# Input_Board.net
KiCad netlist of a schematic drawn in EAGLE
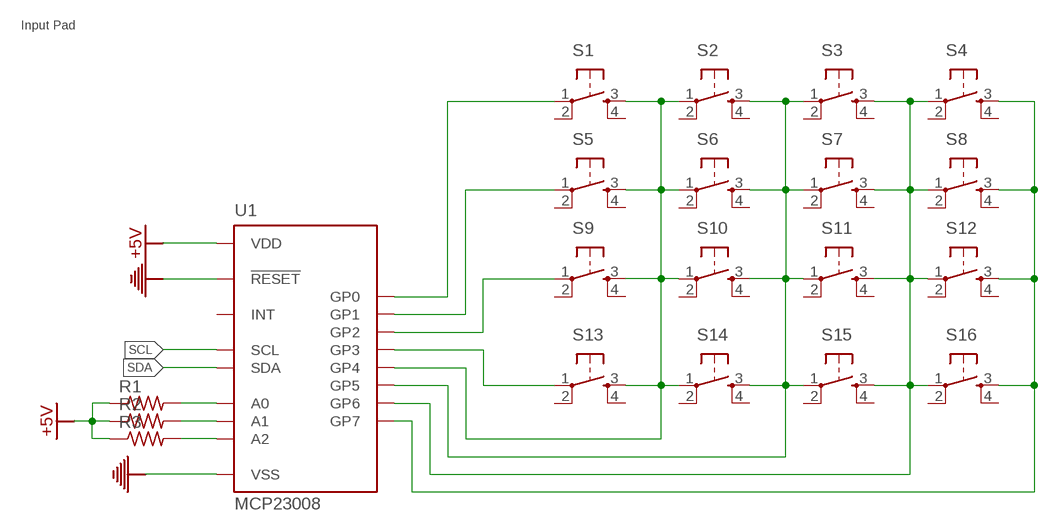
[diagram p0: schematic, sheet 1]

(export (version "E")
  (design (tool "Eeschema 10.0.6"))
  (components
    (comp (ref "R1")
      (value "R-US_M0805")
      (footprint "eagle-import:M0805")
      (libsource (lib "eagle-import") (part "R-US_M0805"))
    )
    (comp (ref "R2")
      (value "R-US_M0805")
      (footprint "eagle-import:M0805")
      (libsource (lib "eagle-import") (part "R-US_M0805"))
    )
    (comp (ref "R3")
      (value "R-US_M0805")
      (footprint "eagle-import:M0805")
      (libsource (lib "eagle-import") (part "R-US_M0805"))
    )
    (comp (ref "S1")
      (value "TAC_SWITCHPTH")
      (footprint "eagle-import:TACTILE-PTH")
      (libsource (lib "eagle-import") (part "TAC_SWITCHPTH"))
    )
    (comp (ref "S2")
      (value "TAC_SWITCHPTH")
      (footprint "eagle-import:TACTILE-PTH")
      (libsource (lib "eagle-import") (part "TAC_SWITCHPTH"))
    )
    (comp (ref "S3")
      (value "TAC_SWITCHPTH")
      (footprint "eagle-import:TACTILE-PTH")
      (libsource (lib "eagle-import") (part "TAC_SWITCHPTH"))
    )
    (comp (ref "S4")
      (value "TAC_SWITCHPTH")
      (footprint "eagle-import:TACTILE-PTH")
      (libsource (lib "eagle-import") (part "TAC_SWITCHPTH"))
    )
    (comp (ref "S5")
      (value "TAC_SWITCHPTH")
      (footprint "eagle-import:TACTILE-PTH")
      (libsource (lib "eagle-import") (part "TAC_SWITCHPTH"))
    )
    (comp (ref "S6")
      (value "TAC_SWITCHPTH")
      (footprint "eagle-import:TACTILE-PTH")
      (libsource (lib "eagle-import") (part "TAC_SWITCHPTH"))
    )
    (comp (ref "S7")
      (value "TAC_SWITCHPTH")
      (footprint "eagle-import:TACTILE-PTH")
      (libsource (lib "eagle-import") (part "TAC_SWITCHPTH"))
    )
    (comp (ref "S8")
      (value "TAC_SWITCHPTH")
      (footprint "eagle-import:TACTILE-PTH")
      (libsource (lib "eagle-import") (part "TAC_SWITCHPTH"))
    )
    (comp (ref "S9")
      (value "TAC_SWITCHPTH")
      (footprint "eagle-import:TACTILE-PTH")
      (libsource (lib "eagle-import") (part "TAC_SWITCHPTH"))
    )
    (comp (ref "S10")
      (value "TAC_SWITCHPTH")
      (footprint "eagle-import:TACTILE-PTH")
      (libsource (lib "eagle-import") (part "TAC_SWITCHPTH"))
    )
    (comp (ref "S11")
      (value "TAC_SWITCHPTH")
      (footprint "eagle-import:TACTILE-PTH")
      (libsource (lib "eagle-import") (part "TAC_SWITCHPTH"))
    )
    (comp (ref "S12")
      (value "TAC_SWITCHPTH")
      (footprint "eagle-import:TACTILE-PTH")
      (libsource (lib "eagle-import") (part "TAC_SWITCHPTH"))
    )
    (comp (ref "S13")
      (value "TAC_SWITCHPTH")
      (footprint "eagle-import:TACTILE-PTH")
      (libsource (lib "eagle-import") (part "TAC_SWITCHPTH"))
    )
    (comp (ref "S14")
      (value "TAC_SWITCHPTH")
      (footprint "eagle-import:TACTILE-PTH")
      (libsource (lib "eagle-import") (part "TAC_SWITCHPTH"))
    )
    (comp (ref "S15")
      (value "TAC_SWITCHPTH")
      (footprint "eagle-import:TACTILE-PTH")
      (libsource (lib "eagle-import") (part "TAC_SWITCHPTH"))
    )
    (comp (ref "S16")
      (value "TAC_SWITCHPTH")
      (footprint "eagle-import:TACTILE-PTH")
      (libsource (lib "eagle-import") (part "TAC_SWITCHPTH"))
    )
    (comp (ref "U1")
      (value "MCP23008")
      (footprint "eagle-import:SOIC")
      (libsource (lib "eagle-import") (part "MCP23008"))
    )
  )
  (nets
    (net (code "1") (name "+5V") (class "Default")
      (node (ref "R1") (pin "1") (pinfunction "1_1") (pintype "passive"))
      (node (ref "R2") (pin "1") (pinfunction "1_1") (pintype "passive"))
      (node (ref "R3") (pin "1") (pinfunction "1_1") (pintype "passive"))
      (node (ref "U1") (pin "P$18") (pinfunction "VDD_P$18") (pintype "power_in"))
    )
    (net (code "2") (name "GND") (class "Default")
      (node (ref "U1") (pin "P$6") (pinfunction "~{RESET}_P$6") (pintype "input"))
      (node (ref "U1") (pin "P$9") (pinfunction "VSS_P$9") (pintype "power_in"))
    )
    (net (code "3") (name "Net-(U1-A0)") (class "Default")
      (node (ref "R1") (pin "2") (pinfunction "2_2") (pintype "passive"))
      (node (ref "U1") (pin "P$5") (pinfunction "A0_P$5") (pintype "input"))
    )
    (net (code "4") (name "Net-(U1-A1)") (class "Default")
      (node (ref "R2") (pin "2") (pinfunction "2_2") (pintype "passive"))
      (node (ref "U1") (pin "P$4") (pinfunction "A1_P$4") (pintype "input"))
    )
    (net (code "5") (name "Net-(U1-A2)") (class "Default")
      (node (ref "R3") (pin "2") (pinfunction "2_2") (pintype "passive"))
      (node (ref "U1") (pin "P$3") (pinfunction "A2_P$3") (pintype "input"))
    )
    (net (code "6") (name "Net-(U1-GP0)") (class "Default")
      (node (ref "S1") (pin "1") (pinfunction "1_1") (pintype "passive"))
      (node (ref "U1") (pin "P$10") (pinfunction "GP0_P$10") (pintype "bidirectional"))
    )
    (net (code "7") (name "Net-(U1-GP1)") (class "Default")
      (node (ref "S5") (pin "1") (pinfunction "1_1") (pintype "passive"))
      (node (ref "U1") (pin "P$11") (pinfunction "GP1_P$11") (pintype "bidirectional"))
    )
    (net (code "8") (name "Net-(U1-GP2)") (class "Default")
      (node (ref "S9") (pin "1") (pinfunction "1_1") (pintype "passive"))
      (node (ref "U1") (pin "P$12") (pinfunction "GP2_P$12") (pintype "bidirectional"))
    )
    (net (code "9") (name "Net-(U1-GP3)") (class "Default")
      (node (ref "S13") (pin "1") (pinfunction "1_1") (pintype "passive"))
      (node (ref "U1") (pin "P$13") (pinfunction "GP3_P$13") (pintype "bidirectional"))
    )
    (net (code "10") (name "Net-(U1-GP4)") (class "Default")
      (node (ref "S1") (pin "3") (pinfunction "3_3") (pintype "passive"))
      (node (ref "S10") (pin "1") (pinfunction "1_1") (pintype "passive"))
      (node (ref "S13") (pin "3") (pinfunction "3_3") (pintype "passive"))
      (node (ref "S14") (pin "1") (pinfunction "1_1") (pintype "passive"))
      (node (ref "S2") (pin "1") (pinfunction "1_1") (pintype "passive"))
      (node (ref "S5") (pin "3") (pinfunction "3_3") (pintype "passive"))
      (node (ref "S6") (pin "1") (pinfunction "1_1") (pintype "passive"))
      (node (ref "S9") (pin "3") (pinfunction "3_3") (pintype "passive"))
      (node (ref "U1") (pin "P$14") (pinfunction "GP4_P$14") (pintype "bidirectional"))
    )
    (net (code "11") (name "Net-(U1-GP5)") (class "Default")
      (node (ref "S10") (pin "3") (pinfunction "3_3") (pintype "passive"))
      (node (ref "S11") (pin "1") (pinfunction "1_1") (pintype "passive"))
      (node (ref "S14") (pin "3") (pinfunction "3_3") (pintype "passive"))
      (node (ref "S15") (pin "1") (pinfunction "1_1") (pintype "passive"))
      (node (ref "S2") (pin "3") (pinfunction "3_3") (pintype "passive"))
      (node (ref "S3") (pin "1") (pinfunction "1_1") (pintype "passive"))
      (node (ref "S6") (pin "3") (pinfunction "3_3") (pintype "passive"))
      (node (ref "S7") (pin "1") (pinfunction "1_1") (pintype "passive"))
      (node (ref "U1") (pin "P$15") (pinfunction "GP5_P$15") (pintype "bidirectional"))
    )
    (net (code "12") (name "Net-(U1-GP6)") (class "Default")
      (node (ref "S11") (pin "3") (pinfunction "3_3") (pintype "passive"))
      (node (ref "S12") (pin "1") (pinfunction "1_1") (pintype "passive"))
      (node (ref "S15") (pin "3") (pinfunction "3_3") (pintype "passive"))
      (node (ref "S16") (pin "1") (pinfunction "1_1") (pintype "passive"))
      (node (ref "S3") (pin "3") (pinfunction "3_3") (pintype "passive"))
      (node (ref "S4") (pin "1") (pinfunction "1_1") (pintype "passive"))
      (node (ref "S7") (pin "3") (pinfunction "3_3") (pintype "passive"))
      (node (ref "S8") (pin "1") (pinfunction "1_1") (pintype "passive"))
      (node (ref "U1") (pin "P$16") (pinfunction "GP6_P$16") (pintype "bidirectional"))
    )
    (net (code "13") (name "Net-(U1-GP7)") (class "Default")
      (node (ref "S12") (pin "3") (pinfunction "3_3") (pintype "passive"))
      (node (ref "S16") (pin "3") (pinfunction "3_3") (pintype "passive"))
      (node (ref "S4") (pin "3") (pinfunction "3_3") (pintype "passive"))
      (node (ref "S8") (pin "3") (pinfunction "3_3") (pintype "passive"))
      (node (ref "U1") (pin "P$17") (pinfunction "GP7_P$17") (pintype "bidirectional"))
    )
    (net (code "14") (name "SCL") (class "Default")
      (node (ref "U1") (pin "P$1") (pinfunction "SCL_P$1") (pintype "input"))
    )
    (net (code "15") (name "SDA") (class "Default")
      (node (ref "U1") (pin "P$2") (pinfunction "SDA_P$2") (pintype "bidirectional"))
    )
    (net (code "16") (name "unconnected-(S1-Pad2)") (class "Default")
      (node (ref "S1") (pin "2") (pinfunction "2_2") (pintype "passive"))
    )
    (net (code "17") (name "unconnected-(S1-Pad4)") (class "Default")
      (node (ref "S1") (pin "4") (pinfunction "4_4") (pintype "passive"))
    )
    (net (code "18") (name "unconnected-(S2-Pad2)") (class "Default")
      (node (ref "S2") (pin "2") (pinfunction "2_2") (pintype "passive"))
    )
    (net (code "19") (name "unconnected-(S2-Pad4)") (class "Default")
      (node (ref "S2") (pin "4") (pinfunction "4_4") (pintype "passive"))
    )
    (net (code "20") (name "unconnected-(S3-Pad2)") (class "Default")
      (node (ref "S3") (pin "2") (pinfunction "2_2") (pintype "passive"))
    )
    (net (code "21") (name "unconnected-(S3-Pad4)") (class "Default")
      (node (ref "S3") (pin "4") (pinfunction "4_4") (pintype "passive"))
    )
    (net (code "22") (name "unconnected-(S4-Pad2)") (class "Default")
      (node (ref "S4") (pin "2") (pinfunction "2_2") (pintype "passive"))
    )
    (net (code "23") (name "unconnected-(S4-Pad4)") (class "Default")
      (node (ref "S4") (pin "4") (pinfunction "4_4") (pintype "passive"))
    )
    (net (code "24") (name "unconnected-(S5-Pad2)") (class "Default")
      (node (ref "S5") (pin "2") (pinfunction "2_2") (pintype "passive"))
    )
    (net (code "25") (name "unconnected-(S5-Pad4)") (class "Default")
      (node (ref "S5") (pin "4") (pinfunction "4_4") (pintype "passive"))
    )
    (net (code "26") (name "unconnected-(S6-Pad2)") (class "Default")
      (node (ref "S6") (pin "2") (pinfunction "2_2") (pintype "passive"))
    )
    (net (code "27") (name "unconnected-(S6-Pad4)") (class "Default")
      (node (ref "S6") (pin "4") (pinfunction "4_4") (pintype "passive"))
    )
    (net (code "28") (name "unconnected-(S7-Pad2)") (class "Default")
      (node (ref "S7") (pin "2") (pinfunction "2_2") (pintype "passive"))
    )
    (net (code "29") (name "unconnected-(S7-Pad4)") (class "Default")
      (node (ref "S7") (pin "4") (pinfunction "4_4") (pintype "passive"))
    )
    (net (code "30") (name "unconnected-(S8-Pad2)") (class "Default")
      (node (ref "S8") (pin "2") (pinfunction "2_2") (pintype "passive"))
    )
    (net (code "31") (name "unconnected-(S8-Pad4)") (class "Default")
      (node (ref "S8") (pin "4") (pinfunction "4_4") (pintype "passive"))
    )
    (net (code "32") (name "unconnected-(S9-Pad2)") (class "Default")
      (node (ref "S9") (pin "2") (pinfunction "2_2") (pintype "passive"))
    )
    (net (code "33") (name "unconnected-(S9-Pad4)") (class "Default")
      (node (ref "S9") (pin "4") (pinfunction "4_4") (pintype "passive"))
    )
    (net (code "34") (name "unconnected-(S10-Pad2)") (class "Default")
      (node (ref "S10") (pin "2") (pinfunction "2_2") (pintype "passive"))
    )
    (net (code "35") (name "unconnected-(S10-Pad4)") (class "Default")
      (node (ref "S10") (pin "4") (pinfunction "4_4") (pintype "passive"))
    )
    (net (code "36") (name "unconnected-(S11-Pad2)") (class "Default")
      (node (ref "S11") (pin "2") (pinfunction "2_2") (pintype "passive"))
    )
    (net (code "37") (name "unconnected-(S11-Pad4)") (class "Default")
      (node (ref "S11") (pin "4") (pinfunction "4_4") (pintype "passive"))
    )
    (net (code "38") (name "unconnected-(S12-Pad2)") (class "Default")
      (node (ref "S12") (pin "2") (pinfunction "2_2") (pintype "passive"))
    )
    (net (code "39") (name "unconnected-(S12-Pad4)") (class "Default")
      (node (ref "S12") (pin "4") (pinfunction "4_4") (pintype "passive"))
    )
    (net (code "40") (name "unconnected-(S13-Pad2)") (class "Default")
      (node (ref "S13") (pin "2") (pinfunction "2_2") (pintype "passive"))
    )
    (net (code "41") (name "unconnected-(S13-Pad4)") (class "Default")
      (node (ref "S13") (pin "4") (pinfunction "4_4") (pintype "passive"))
    )
    (net (code "42") (name "unconnected-(S14-Pad2)") (class "Default")
      (node (ref "S14") (pin "2") (pinfunction "2_2") (pintype "passive"))
    )
    (net (code "43") (name "unconnected-(S14-Pad4)") (class "Default")
      (node (ref "S14") (pin "4") (pinfunction "4_4") (pintype "passive"))
    )
    (net (code "44") (name "unconnected-(S15-Pad2)") (class "Default")
      (node (ref "S15") (pin "2") (pinfunction "2_2") (pintype "passive"))
    )
    (net (code "45") (name "unconnected-(S15-Pad4)") (class "Default")
      (node (ref "S15") (pin "4") (pinfunction "4_4") (pintype "passive"))
    )
    (net (code "46") (name "unconnected-(S16-Pad2)") (class "Default")
      (node (ref "S16") (pin "2") (pinfunction "2_2") (pintype "passive"))
    )
    (net (code "47") (name "unconnected-(S16-Pad4)") (class "Default")
      (node (ref "S16") (pin "4") (pinfunction "4_4") (pintype "passive"))
    )
    (net (code "48") (name "unconnected-(U1-INT-PadP$8)") (class "Default")
      (node (ref "U1") (pin "P$8") (pinfunction "INT_P$8") (pintype "output"))
    )
  )
)
